# lat_stm_rpi.net
KiCad netlist of a schematic drawn in EAGLE
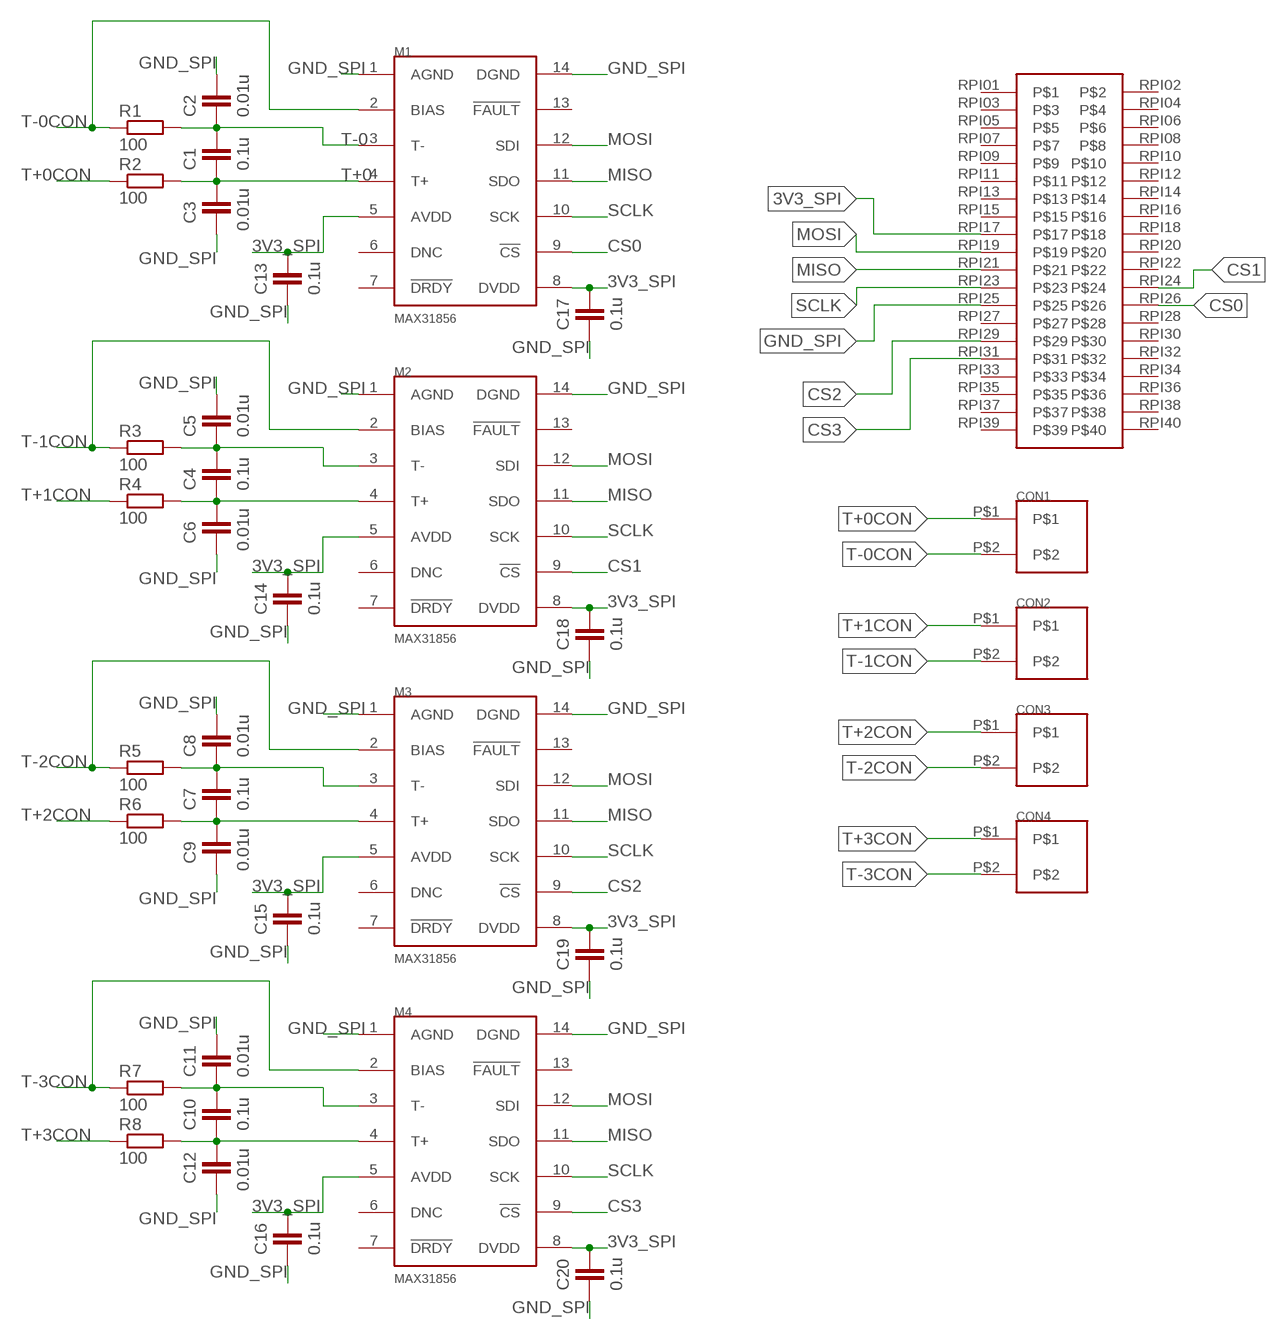
[diagram p0: schematic, sheet 1]

(export (version "E")
  (design (tool "Eeschema 10.0.6"))
  (components
    (comp (ref "C1")
      (value "0.1u")
      (footprint "eagle-import:C0603")
      (libsource (lib "eagle-import") (part "C-EUC0603"))
    )
    (comp (ref "C2")
      (value "0.01u")
      (footprint "eagle-import:C0603")
      (libsource (lib "eagle-import") (part "C-EUC0603"))
    )
    (comp (ref "C3")
      (value "0.01u")
      (footprint "eagle-import:C0603")
      (libsource (lib "eagle-import") (part "C-EUC0603"))
    )
    (comp (ref "C4")
      (value "0.1u")
      (footprint "eagle-import:C0603")
      (libsource (lib "eagle-import") (part "C-EUC0603"))
    )
    (comp (ref "C5")
      (value "0.01u")
      (footprint "eagle-import:C0603")
      (libsource (lib "eagle-import") (part "C-EUC0603"))
    )
    (comp (ref "C6")
      (value "0.01u")
      (footprint "eagle-import:C0603")
      (libsource (lib "eagle-import") (part "C-EUC0603"))
    )
    (comp (ref "C7")
      (value "0.1u")
      (footprint "eagle-import:C0603")
      (libsource (lib "eagle-import") (part "C-EUC0603"))
    )
    (comp (ref "C8")
      (value "0.01u")
      (footprint "eagle-import:C0603")
      (libsource (lib "eagle-import") (part "C-EUC0603"))
    )
    (comp (ref "C9")
      (value "0.01u")
      (footprint "eagle-import:C0603")
      (libsource (lib "eagle-import") (part "C-EUC0603"))
    )
    (comp (ref "C10")
      (value "0.1u")
      (footprint "eagle-import:C0603")
      (libsource (lib "eagle-import") (part "C-EUC0603"))
    )
    (comp (ref "C11")
      (value "0.01u")
      (footprint "eagle-import:C0603")
      (libsource (lib "eagle-import") (part "C-EUC0603"))
    )
    (comp (ref "C12")
      (value "0.01u")
      (footprint "eagle-import:C0603")
      (libsource (lib "eagle-import") (part "C-EUC0603"))
    )
    (comp (ref "C13")
      (value "0.1u")
      (footprint "eagle-import:C0603")
      (libsource (lib "eagle-import") (part "C-EUC0603"))
    )
    (comp (ref "C14")
      (value "0.1u")
      (footprint "eagle-import:C0603")
      (libsource (lib "eagle-import") (part "C-EUC0603"))
    )
    (comp (ref "C15")
      (value "0.1u")
      (footprint "eagle-import:C0603")
      (libsource (lib "eagle-import") (part "C-EUC0603"))
    )
    (comp (ref "C16")
      (value "0.1u")
      (footprint "eagle-import:C0603")
      (libsource (lib "eagle-import") (part "C-EUC0603"))
    )
    (comp (ref "C17")
      (value "0.1u")
      (footprint "eagle-import:C0603")
      (libsource (lib "eagle-import") (part "C-EUC0603"))
    )
    (comp (ref "C18")
      (value "0.1u")
      (footprint "eagle-import:C0603")
      (libsource (lib "eagle-import") (part "C-EUC0603"))
    )
    (comp (ref "C19")
      (value "0.1u")
      (footprint "eagle-import:C0603")
      (libsource (lib "eagle-import") (part "C-EUC0603"))
    )
    (comp (ref "C20")
      (value "0.1u")
      (footprint "eagle-import:C0603")
      (libsource (lib "eagle-import") (part "C-EUC0603"))
    )
    (comp (ref "CON1")
      (value "893-1332")
      (footprint "eagle-import:893-1332")
      (libsource (lib "eagle-import") (part "893-1332"))
    )
    (comp (ref "CON2")
      (value "893-1332")
      (footprint "eagle-import:893-1332")
      (libsource (lib "eagle-import") (part "893-1332"))
    )
    (comp (ref "CON3")
      (value "893-1332")
      (footprint "eagle-import:893-1332")
      (libsource (lib "eagle-import") (part "893-1332"))
    )
    (comp (ref "CON4")
      (value "893-1332")
      (footprint "eagle-import:893-1332")
      (libsource (lib "eagle-import") (part "893-1332"))
    )
    (comp (ref "M1")
      (value "MAX31856")
      (footprint "eagle-import:TSSOP14")
      (libsource (lib "eagle-import") (part "MAX31856"))
    )
    (comp (ref "M2")
      (value "MAX31856")
      (footprint "eagle-import:TSSOP14")
      (libsource (lib "eagle-import") (part "MAX31856"))
    )
    (comp (ref "M3")
      (value "MAX31856")
      (footprint "eagle-import:TSSOP14")
      (libsource (lib "eagle-import") (part "MAX31856"))
    )
    (comp (ref "M4")
      (value "MAX31856")
      (footprint "eagle-import:TSSOP14")
      (libsource (lib "eagle-import") (part "MAX31856"))
    )
    (comp (ref "R1")
      (value "100")
      (footprint "eagle-import:R0603")
      (libsource (lib "eagle-import") (part "R-EU_R0603"))
    )
    (comp (ref "R2")
      (value "100")
      (footprint "eagle-import:R0603")
      (libsource (lib "eagle-import") (part "R-EU_R0603"))
    )
    (comp (ref "R3")
      (value "100")
      (footprint "eagle-import:R0603")
      (libsource (lib "eagle-import") (part "R-EU_R0603"))
    )
    (comp (ref "R4")
      (value "100")
      (footprint "eagle-import:R0603")
      (libsource (lib "eagle-import") (part "R-EU_R0603"))
    )
    (comp (ref "R5")
      (value "100")
      (footprint "eagle-import:R0603")
      (libsource (lib "eagle-import") (part "R-EU_R0603"))
    )
    (comp (ref "R6")
      (value "100")
      (footprint "eagle-import:R0603")
      (libsource (lib "eagle-import") (part "R-EU_R0603"))
    )
    (comp (ref "R7")
      (value "100")
      (footprint "eagle-import:R0603")
      (libsource (lib "eagle-import") (part "R-EU_R0603"))
    )
    (comp (ref "R8")
      (value "100")
      (footprint "eagle-import:R0603")
      (libsource (lib "eagle-import") (part "R-EU_R0603"))
    )
    (comp (ref "RPC1")
      (value "RPI_CON")
      (footprint "eagle-import:RPI_CON")
      (libsource (lib "eagle-import") (part "RPI_CON"))
    )
  )
  (nets
    (net (code "1") (name "/T+0") (class "Default")
      (node (ref "C1") (pin "2") (pinfunction "2_2") (pintype "passive"))
      (node (ref "C3") (pin "1") (pinfunction "1_1") (pintype "passive"))
      (node (ref "M1") (pin "4") (pinfunction "T+_4") (pintype "bidirectional"))
      (node (ref "R2") (pin "2") (pinfunction "2_2") (pintype "passive"))
    )
    (net (code "2") (name "/T-0") (class "Default")
      (node (ref "C1") (pin "1") (pinfunction "1_1") (pintype "passive"))
      (node (ref "C2") (pin "2") (pinfunction "2_2") (pintype "passive"))
      (node (ref "M1") (pin "3") (pinfunction "T-_3") (pintype "bidirectional"))
      (node (ref "R1") (pin "2") (pinfunction "2_2") (pintype "passive"))
    )
    (net (code "3") (name "3V3_SPI") (class "Default")
      (node (ref "C13") (pin "1") (pinfunction "1_1") (pintype "passive"))
      (node (ref "C14") (pin "1") (pinfunction "1_1") (pintype "passive"))
      (node (ref "C15") (pin "1") (pinfunction "1_1") (pintype "passive"))
      (node (ref "C16") (pin "1") (pinfunction "1_1") (pintype "passive"))
      (node (ref "C17") (pin "1") (pinfunction "1_1") (pintype "passive"))
      (node (ref "C18") (pin "1") (pinfunction "1_1") (pintype "passive"))
      (node (ref "C19") (pin "1") (pinfunction "1_1") (pintype "passive"))
      (node (ref "C20") (pin "1") (pinfunction "1_1") (pintype "passive"))
      (node (ref "M1") (pin "5") (pinfunction "AVDD_5") (pintype "bidirectional"))
      (node (ref "M1") (pin "8") (pinfunction "DVDD_8") (pintype "bidirectional"))
      (node (ref "M2") (pin "5") (pinfunction "AVDD_5") (pintype "bidirectional"))
      (node (ref "M2") (pin "8") (pinfunction "DVDD_8") (pintype "bidirectional"))
      (node (ref "M3") (pin "5") (pinfunction "AVDD_5") (pintype "bidirectional"))
      (node (ref "M3") (pin "8") (pinfunction "DVDD_8") (pintype "bidirectional"))
      (node (ref "M4") (pin "5") (pinfunction "AVDD_5") (pintype "bidirectional"))
      (node (ref "M4") (pin "8") (pinfunction "DVDD_8") (pintype "bidirectional"))
      (node (ref "RPC1") (pin "RPI17") (pinfunction "P$17_RPI17") (pintype "bidirectional"))
    )
    (net (code "4") (name "CS0") (class "Default")
      (node (ref "M1") (pin "9") (pinfunction "~{CS}_9") (pintype "bidirectional"))
      (node (ref "RPC1") (pin "RPI26") (pinfunction "P$26_RPI26") (pintype "bidirectional"))
    )
    (net (code "5") (name "CS1") (class "Default")
      (node (ref "M2") (pin "9") (pinfunction "~{CS}_9") (pintype "bidirectional"))
      (node (ref "RPC1") (pin "RPI24") (pinfunction "P$24_RPI24") (pintype "bidirectional"))
    )
    (net (code "6") (name "CS2") (class "Default")
      (node (ref "M3") (pin "9") (pinfunction "~{CS}_9") (pintype "bidirectional"))
      (node (ref "RPC1") (pin "RPI29") (pinfunction "P$29_RPI29") (pintype "bidirectional"))
    )
    (net (code "7") (name "CS3") (class "Default")
      (node (ref "M4") (pin "9") (pinfunction "~{CS}_9") (pintype "bidirectional"))
      (node (ref "RPC1") (pin "RPI31") (pinfunction "P$31_RPI31") (pintype "bidirectional"))
    )
    (net (code "8") (name "GND_SPI") (class "Default")
      (node (ref "C11") (pin "1") (pinfunction "1_1") (pintype "passive"))
      (node (ref "C12") (pin "2") (pinfunction "2_2") (pintype "passive"))
      (node (ref "C13") (pin "2") (pinfunction "2_2") (pintype "passive"))
      (node (ref "C14") (pin "2") (pinfunction "2_2") (pintype "passive"))
      (node (ref "C15") (pin "2") (pinfunction "2_2") (pintype "passive"))
      (node (ref "C16") (pin "2") (pinfunction "2_2") (pintype "passive"))
      (node (ref "C17") (pin "2") (pinfunction "2_2") (pintype "passive"))
      (node (ref "C18") (pin "2") (pinfunction "2_2") (pintype "passive"))
      (node (ref "C19") (pin "2") (pinfunction "2_2") (pintype "passive"))
      (node (ref "C2") (pin "1") (pinfunction "1_1") (pintype "passive"))
      (node (ref "C20") (pin "2") (pinfunction "2_2") (pintype "passive"))
      (node (ref "C3") (pin "2") (pinfunction "2_2") (pintype "passive"))
      (node (ref "C5") (pin "1") (pinfunction "1_1") (pintype "passive"))
      (node (ref "C6") (pin "2") (pinfunction "2_2") (pintype "passive"))
      (node (ref "C8") (pin "1") (pinfunction "1_1") (pintype "passive"))
      (node (ref "C9") (pin "2") (pinfunction "2_2") (pintype "passive"))
      (node (ref "M1") (pin "1") (pinfunction "AGND_1") (pintype "bidirectional"))
      (node (ref "M1") (pin "14") (pinfunction "DGND_14") (pintype "bidirectional"))
      (node (ref "M2") (pin "1") (pinfunction "AGND_1") (pintype "bidirectional"))
      (node (ref "M2") (pin "14") (pinfunction "DGND_14") (pintype "bidirectional"))
      (node (ref "M3") (pin "1") (pinfunction "AGND_1") (pintype "bidirectional"))
      (node (ref "M3") (pin "14") (pinfunction "DGND_14") (pintype "bidirectional"))
      (node (ref "M4") (pin "1") (pinfunction "AGND_1") (pintype "bidirectional"))
      (node (ref "M4") (pin "14") (pinfunction "DGND_14") (pintype "bidirectional"))
      (node (ref "RPC1") (pin "RPI25") (pinfunction "P$25_RPI25") (pintype "bidirectional"))
    )
    (net (code "9") (name "MISO") (class "Default")
      (node (ref "M1") (pin "11") (pinfunction "SDO_11") (pintype "bidirectional"))
      (node (ref "M2") (pin "11") (pinfunction "SDO_11") (pintype "bidirectional"))
      (node (ref "M3") (pin "11") (pinfunction "SDO_11") (pintype "bidirectional"))
      (node (ref "M4") (pin "11") (pinfunction "SDO_11") (pintype "bidirectional"))
      (node (ref "RPC1") (pin "RPI21") (pinfunction "P$21_RPI21") (pintype "bidirectional"))
    )
    (net (code "10") (name "MOSI") (class "Default")
      (node (ref "M1") (pin "12") (pinfunction "SDI_12") (pintype "bidirectional"))
      (node (ref "M2") (pin "12") (pinfunction "SDI_12") (pintype "bidirectional"))
      (node (ref "M3") (pin "12") (pinfunction "SDI_12") (pintype "bidirectional"))
      (node (ref "M4") (pin "12") (pinfunction "SDI_12") (pintype "bidirectional"))
      (node (ref "RPC1") (pin "RPI19") (pinfunction "P$19_RPI19") (pintype "bidirectional"))
    )
    (net (code "11") (name "Net-(M2-T+)") (class "Default")
      (node (ref "C4") (pin "2") (pinfunction "2_2") (pintype "passive"))
      (node (ref "C6") (pin "1") (pinfunction "1_1") (pintype "passive"))
      (node (ref "M2") (pin "4") (pinfunction "T+_4") (pintype "bidirectional"))
      (node (ref "R4") (pin "2") (pinfunction "2_2") (pintype "passive"))
    )
    (net (code "12") (name "Net-(M2-T-)") (class "Default")
      (node (ref "C4") (pin "1") (pinfunction "1_1") (pintype "passive"))
      (node (ref "C5") (pin "2") (pinfunction "2_2") (pintype "passive"))
      (node (ref "M2") (pin "3") (pinfunction "T-_3") (pintype "bidirectional"))
      (node (ref "R3") (pin "2") (pinfunction "2_2") (pintype "passive"))
    )
    (net (code "13") (name "Net-(M3-T+)") (class "Default")
      (node (ref "C7") (pin "2") (pinfunction "2_2") (pintype "passive"))
      (node (ref "C9") (pin "1") (pinfunction "1_1") (pintype "passive"))
      (node (ref "M3") (pin "4") (pinfunction "T+_4") (pintype "bidirectional"))
      (node (ref "R6") (pin "2") (pinfunction "2_2") (pintype "passive"))
    )
    (net (code "14") (name "Net-(M3-T-)") (class "Default")
      (node (ref "C7") (pin "1") (pinfunction "1_1") (pintype "passive"))
      (node (ref "C8") (pin "2") (pinfunction "2_2") (pintype "passive"))
      (node (ref "M3") (pin "3") (pinfunction "T-_3") (pintype "bidirectional"))
      (node (ref "R5") (pin "2") (pinfunction "2_2") (pintype "passive"))
    )
    (net (code "15") (name "Net-(M4-T+)") (class "Default")
      (node (ref "C10") (pin "2") (pinfunction "2_2") (pintype "passive"))
      (node (ref "C12") (pin "1") (pinfunction "1_1") (pintype "passive"))
      (node (ref "M4") (pin "4") (pinfunction "T+_4") (pintype "bidirectional"))
      (node (ref "R8") (pin "2") (pinfunction "2_2") (pintype "passive"))
    )
    (net (code "16") (name "Net-(M4-T-)") (class "Default")
      (node (ref "C10") (pin "1") (pinfunction "1_1") (pintype "passive"))
      (node (ref "C11") (pin "2") (pinfunction "2_2") (pintype "passive"))
      (node (ref "M4") (pin "3") (pinfunction "T-_3") (pintype "bidirectional"))
      (node (ref "R7") (pin "2") (pinfunction "2_2") (pintype "passive"))
    )
    (net (code "17") (name "SCLK") (class "Default")
      (node (ref "M1") (pin "10") (pinfunction "SCK_10") (pintype "bidirectional"))
      (node (ref "M2") (pin "10") (pinfunction "SCK_10") (pintype "bidirectional"))
      (node (ref "M3") (pin "10") (pinfunction "SCK_10") (pintype "bidirectional"))
      (node (ref "M4") (pin "10") (pinfunction "SCK_10") (pintype "bidirectional"))
      (node (ref "RPC1") (pin "RPI23") (pinfunction "P$23_RPI23") (pintype "bidirectional"))
    )
    (net (code "18") (name "T+0CON") (class "Default")
      (node (ref "CON1") (pin "P$1") (pinfunction "P$1_P$1") (pintype "bidirectional"))
      (node (ref "R2") (pin "1") (pinfunction "1_1") (pintype "passive"))
    )
    (net (code "19") (name "T+1CON") (class "Default")
      (node (ref "CON2") (pin "P$1") (pinfunction "P$1_P$1") (pintype "bidirectional"))
      (node (ref "R4") (pin "1") (pinfunction "1_1") (pintype "passive"))
    )
    (net (code "20") (name "T+2CON") (class "Default")
      (node (ref "CON3") (pin "P$1") (pinfunction "P$1_P$1") (pintype "bidirectional"))
      (node (ref "R6") (pin "1") (pinfunction "1_1") (pintype "passive"))
    )
    (net (code "21") (name "T+3CON") (class "Default")
      (node (ref "CON4") (pin "P$1") (pinfunction "P$1_P$1") (pintype "bidirectional"))
      (node (ref "R8") (pin "1") (pinfunction "1_1") (pintype "passive"))
    )
    (net (code "22") (name "T-0CON") (class "Default")
      (node (ref "CON1") (pin "P$2") (pinfunction "P$2_P$2") (pintype "bidirectional"))
      (node (ref "M1") (pin "2") (pinfunction "BIAS_2") (pintype "bidirectional"))
      (node (ref "R1") (pin "1") (pinfunction "1_1") (pintype "passive"))
    )
    (net (code "23") (name "T-1CON") (class "Default")
      (node (ref "CON2") (pin "P$2") (pinfunction "P$2_P$2") (pintype "bidirectional"))
      (node (ref "M2") (pin "2") (pinfunction "BIAS_2") (pintype "bidirectional"))
      (node (ref "R3") (pin "1") (pinfunction "1_1") (pintype "passive"))
    )
    (net (code "24") (name "T-2CON") (class "Default")
      (node (ref "CON3") (pin "P$2") (pinfunction "P$2_P$2") (pintype "bidirectional"))
      (node (ref "M3") (pin "2") (pinfunction "BIAS_2") (pintype "bidirectional"))
      (node (ref "R5") (pin "1") (pinfunction "1_1") (pintype "passive"))
    )
    (net (code "25") (name "T-3CON") (class "Default")
      (node (ref "CON4") (pin "P$2") (pinfunction "P$2_P$2") (pintype "bidirectional"))
      (node (ref "M4") (pin "2") (pinfunction "BIAS_2") (pintype "bidirectional"))
      (node (ref "R7") (pin "1") (pinfunction "1_1") (pintype "passive"))
    )
    (net (code "26") (name "unconnected-(M1-DNC-Pad6)") (class "Default")
      (node (ref "M1") (pin "6") (pinfunction "DNC_6") (pintype "bidirectional"))
    )
    (net (code "27") (name "unconnected-(M1-~{DRDY}-Pad7)") (class "Default")
      (node (ref "M1") (pin "7") (pinfunction "~{DRDY}_7") (pintype "bidirectional"))
    )
    (net (code "28") (name "unconnected-(M1-~{FAULT}-Pad13)") (class "Default")
      (node (ref "M1") (pin "13") (pinfunction "~{FAULT}_13") (pintype "bidirectional"))
    )
    (net (code "29") (name "unconnected-(M2-DNC-Pad6)") (class "Default")
      (node (ref "M2") (pin "6") (pinfunction "DNC_6") (pintype "bidirectional"))
    )
    (net (code "30") (name "unconnected-(M2-~{DRDY}-Pad7)") (class "Default")
      (node (ref "M2") (pin "7") (pinfunction "~{DRDY}_7") (pintype "bidirectional"))
    )
    (net (code "31") (name "unconnected-(M2-~{FAULT}-Pad13)") (class "Default")
      (node (ref "M2") (pin "13") (pinfunction "~{FAULT}_13") (pintype "bidirectional"))
    )
    (net (code "32") (name "unconnected-(M3-DNC-Pad6)") (class "Default")
      (node (ref "M3") (pin "6") (pinfunction "DNC_6") (pintype "bidirectional"))
    )
    (net (code "33") (name "unconnected-(M3-~{DRDY}-Pad7)") (class "Default")
      (node (ref "M3") (pin "7") (pinfunction "~{DRDY}_7") (pintype "bidirectional"))
    )
    (net (code "34") (name "unconnected-(M3-~{FAULT}-Pad13)") (class "Default")
      (node (ref "M3") (pin "13") (pinfunction "~{FAULT}_13") (pintype "bidirectional"))
    )
    (net (code "35") (name "unconnected-(M4-DNC-Pad6)") (class "Default")
      (node (ref "M4") (pin "6") (pinfunction "DNC_6") (pintype "bidirectional"))
    )
    (net (code "36") (name "unconnected-(M4-~{DRDY}-Pad7)") (class "Default")
      (node (ref "M4") (pin "7") (pinfunction "~{DRDY}_7") (pintype "bidirectional"))
    )
    (net (code "37") (name "unconnected-(M4-~{FAULT}-Pad13)") (class "Default")
      (node (ref "M4") (pin "13") (pinfunction "~{FAULT}_13") (pintype "bidirectional"))
    )
    (net (code "38") (name "unconnected-(RPC1-P$1-PadRPI01)") (class "Default")
      (node (ref "RPC1") (pin "RPI01") (pinfunction "P$1_RPI01") (pintype "bidirectional"))
    )
    (net (code "39") (name "unconnected-(RPC1-P$2-PadRPI02)") (class "Default")
      (node (ref "RPC1") (pin "RPI02") (pinfunction "P$2_RPI02") (pintype "bidirectional"))
    )
    (net (code "40") (name "unconnected-(RPC1-P$3-PadRPI03)") (class "Default")
      (node (ref "RPC1") (pin "RPI03") (pinfunction "P$3_RPI03") (pintype "bidirectional"))
    )
    (net (code "41") (name "unconnected-(RPC1-P$4-PadRPI04)") (class "Default")
      (node (ref "RPC1") (pin "RPI04") (pinfunction "P$4_RPI04") (pintype "bidirectional"))
    )
    (net (code "42") (name "unconnected-(RPC1-P$5-PadRPI05)") (class "Default")
      (node (ref "RPC1") (pin "RPI05") (pinfunction "P$5_RPI05") (pintype "bidirectional"))
    )
    (net (code "43") (name "unconnected-(RPC1-P$6-PadRPI06)") (class "Default")
      (node (ref "RPC1") (pin "RPI06") (pinfunction "P$6_RPI06") (pintype "bidirectional"))
    )
    (net (code "44") (name "unconnected-(RPC1-P$7-PadRPI07)") (class "Default")
      (node (ref "RPC1") (pin "RPI07") (pinfunction "P$7_RPI07") (pintype "bidirectional"))
    )
    (net (code "45") (name "unconnected-(RPC1-P$8-PadRPI08)") (class "Default")
      (node (ref "RPC1") (pin "RPI08") (pinfunction "P$8_RPI08") (pintype "bidirectional"))
    )
    (net (code "46") (name "unconnected-(RPC1-P$9-PadRPI09)") (class "Default")
      (node (ref "RPC1") (pin "RPI09") (pinfunction "P$9_RPI09") (pintype "bidirectional"))
    )
    (net (code "47") (name "unconnected-(RPC1-P$10-PadRPI10)") (class "Default")
      (node (ref "RPC1") (pin "RPI10") (pinfunction "P$10_RPI10") (pintype "bidirectional"))
    )
    (net (code "48") (name "unconnected-(RPC1-P$11-PadRPI11)") (class "Default")
      (node (ref "RPC1") (pin "RPI11") (pinfunction "P$11_RPI11") (pintype "bidirectional"))
    )
    (net (code "49") (name "unconnected-(RPC1-P$12-PadRPI12)") (class "Default")
      (node (ref "RPC1") (pin "RPI12") (pinfunction "P$12_RPI12") (pintype "bidirectional"))
    )
    (net (code "50") (name "unconnected-(RPC1-P$13-PadRPI13)") (class "Default")
      (node (ref "RPC1") (pin "RPI13") (pinfunction "P$13_RPI13") (pintype "bidirectional"))
    )
    (net (code "51") (name "unconnected-(RPC1-P$14-PadRPI14)") (class "Default")
      (node (ref "RPC1") (pin "RPI14") (pinfunction "P$14_RPI14") (pintype "bidirectional"))
    )
    (net (code "52") (name "unconnected-(RPC1-P$15-PadRPI15)") (class "Default")
      (node (ref "RPC1") (pin "RPI15") (pinfunction "P$15_RPI15") (pintype "bidirectional"))
    )
    (net (code "53") (name "unconnected-(RPC1-P$16-PadRPI16)") (class "Default")
      (node (ref "RPC1") (pin "RPI16") (pinfunction "P$16_RPI16") (pintype "bidirectional"))
    )
    (net (code "54") (name "unconnected-(RPC1-P$18-PadRPI18)") (class "Default")
      (node (ref "RPC1") (pin "RPI18") (pinfunction "P$18_RPI18") (pintype "bidirectional"))
    )
    (net (code "55") (name "unconnected-(RPC1-P$20-PadRPI20)") (class "Default")
      (node (ref "RPC1") (pin "RPI20") (pinfunction "P$20_RPI20") (pintype "bidirectional"))
    )
    (net (code "56") (name "unconnected-(RPC1-P$22-PadRPI22)") (class "Default")
      (node (ref "RPC1") (pin "RPI22") (pinfunction "P$22_RPI22") (pintype "bidirectional"))
    )
    (net (code "57") (name "unconnected-(RPC1-P$27-PadRPI27)") (class "Default")
      (node (ref "RPC1") (pin "RPI27") (pinfunction "P$27_RPI27") (pintype "bidirectional"))
    )
    (net (code "58") (name "unconnected-(RPC1-P$28-PadRPI28)") (class "Default")
      (node (ref "RPC1") (pin "RPI28") (pinfunction "P$28_RPI28") (pintype "bidirectional"))
    )
    (net (code "59") (name "unconnected-(RPC1-P$30-PadRPI30)") (class "Default")
      (node (ref "RPC1") (pin "RPI30") (pinfunction "P$30_RPI30") (pintype "bidirectional"))
    )
    (net (code "60") (name "unconnected-(RPC1-P$32-PadRPI32)") (class "Default")
      (node (ref "RPC1") (pin "RPI32") (pinfunction "P$32_RPI32") (pintype "bidirectional"))
    )
    (net (code "61") (name "unconnected-(RPC1-P$33-PadRPI33)") (class "Default")
      (node (ref "RPC1") (pin "RPI33") (pinfunction "P$33_RPI33") (pintype "bidirectional"))
    )
    (net (code "62") (name "unconnected-(RPC1-P$34-PadRPI34)") (class "Default")
      (node (ref "RPC1") (pin "RPI34") (pinfunction "P$34_RPI34") (pintype "bidirectional"))
    )
    (net (code "63") (name "unconnected-(RPC1-P$35-PadRPI35)") (class "Default")
      (node (ref "RPC1") (pin "RPI35") (pinfunction "P$35_RPI35") (pintype "bidirectional"))
    )
    (net (code "64") (name "unconnected-(RPC1-P$36-PadRPI36)") (class "Default")
      (node (ref "RPC1") (pin "RPI36") (pinfunction "P$36_RPI36") (pintype "bidirectional"))
    )
    (net (code "65") (name "unconnected-(RPC1-P$37-PadRPI37)") (class "Default")
      (node (ref "RPC1") (pin "RPI37") (pinfunction "P$37_RPI37") (pintype "bidirectional"))
    )
    (net (code "66") (name "unconnected-(RPC1-P$38-PadRPI38)") (class "Default")
      (node (ref "RPC1") (pin "RPI38") (pinfunction "P$38_RPI38") (pintype "bidirectional"))
    )
    (net (code "67") (name "unconnected-(RPC1-P$39-PadRPI39)") (class "Default")
      (node (ref "RPC1") (pin "RPI39") (pinfunction "P$39_RPI39") (pintype "bidirectional"))
    )
    (net (code "68") (name "unconnected-(RPC1-P$40-PadRPI40)") (class "Default")
      (node (ref "RPC1") (pin "RPI40") (pinfunction "P$40_RPI40") (pintype "bidirectional"))
    )
  )
)
